# SchemaB.net
KiCad netlist of a schematic drawn in Altium Designer
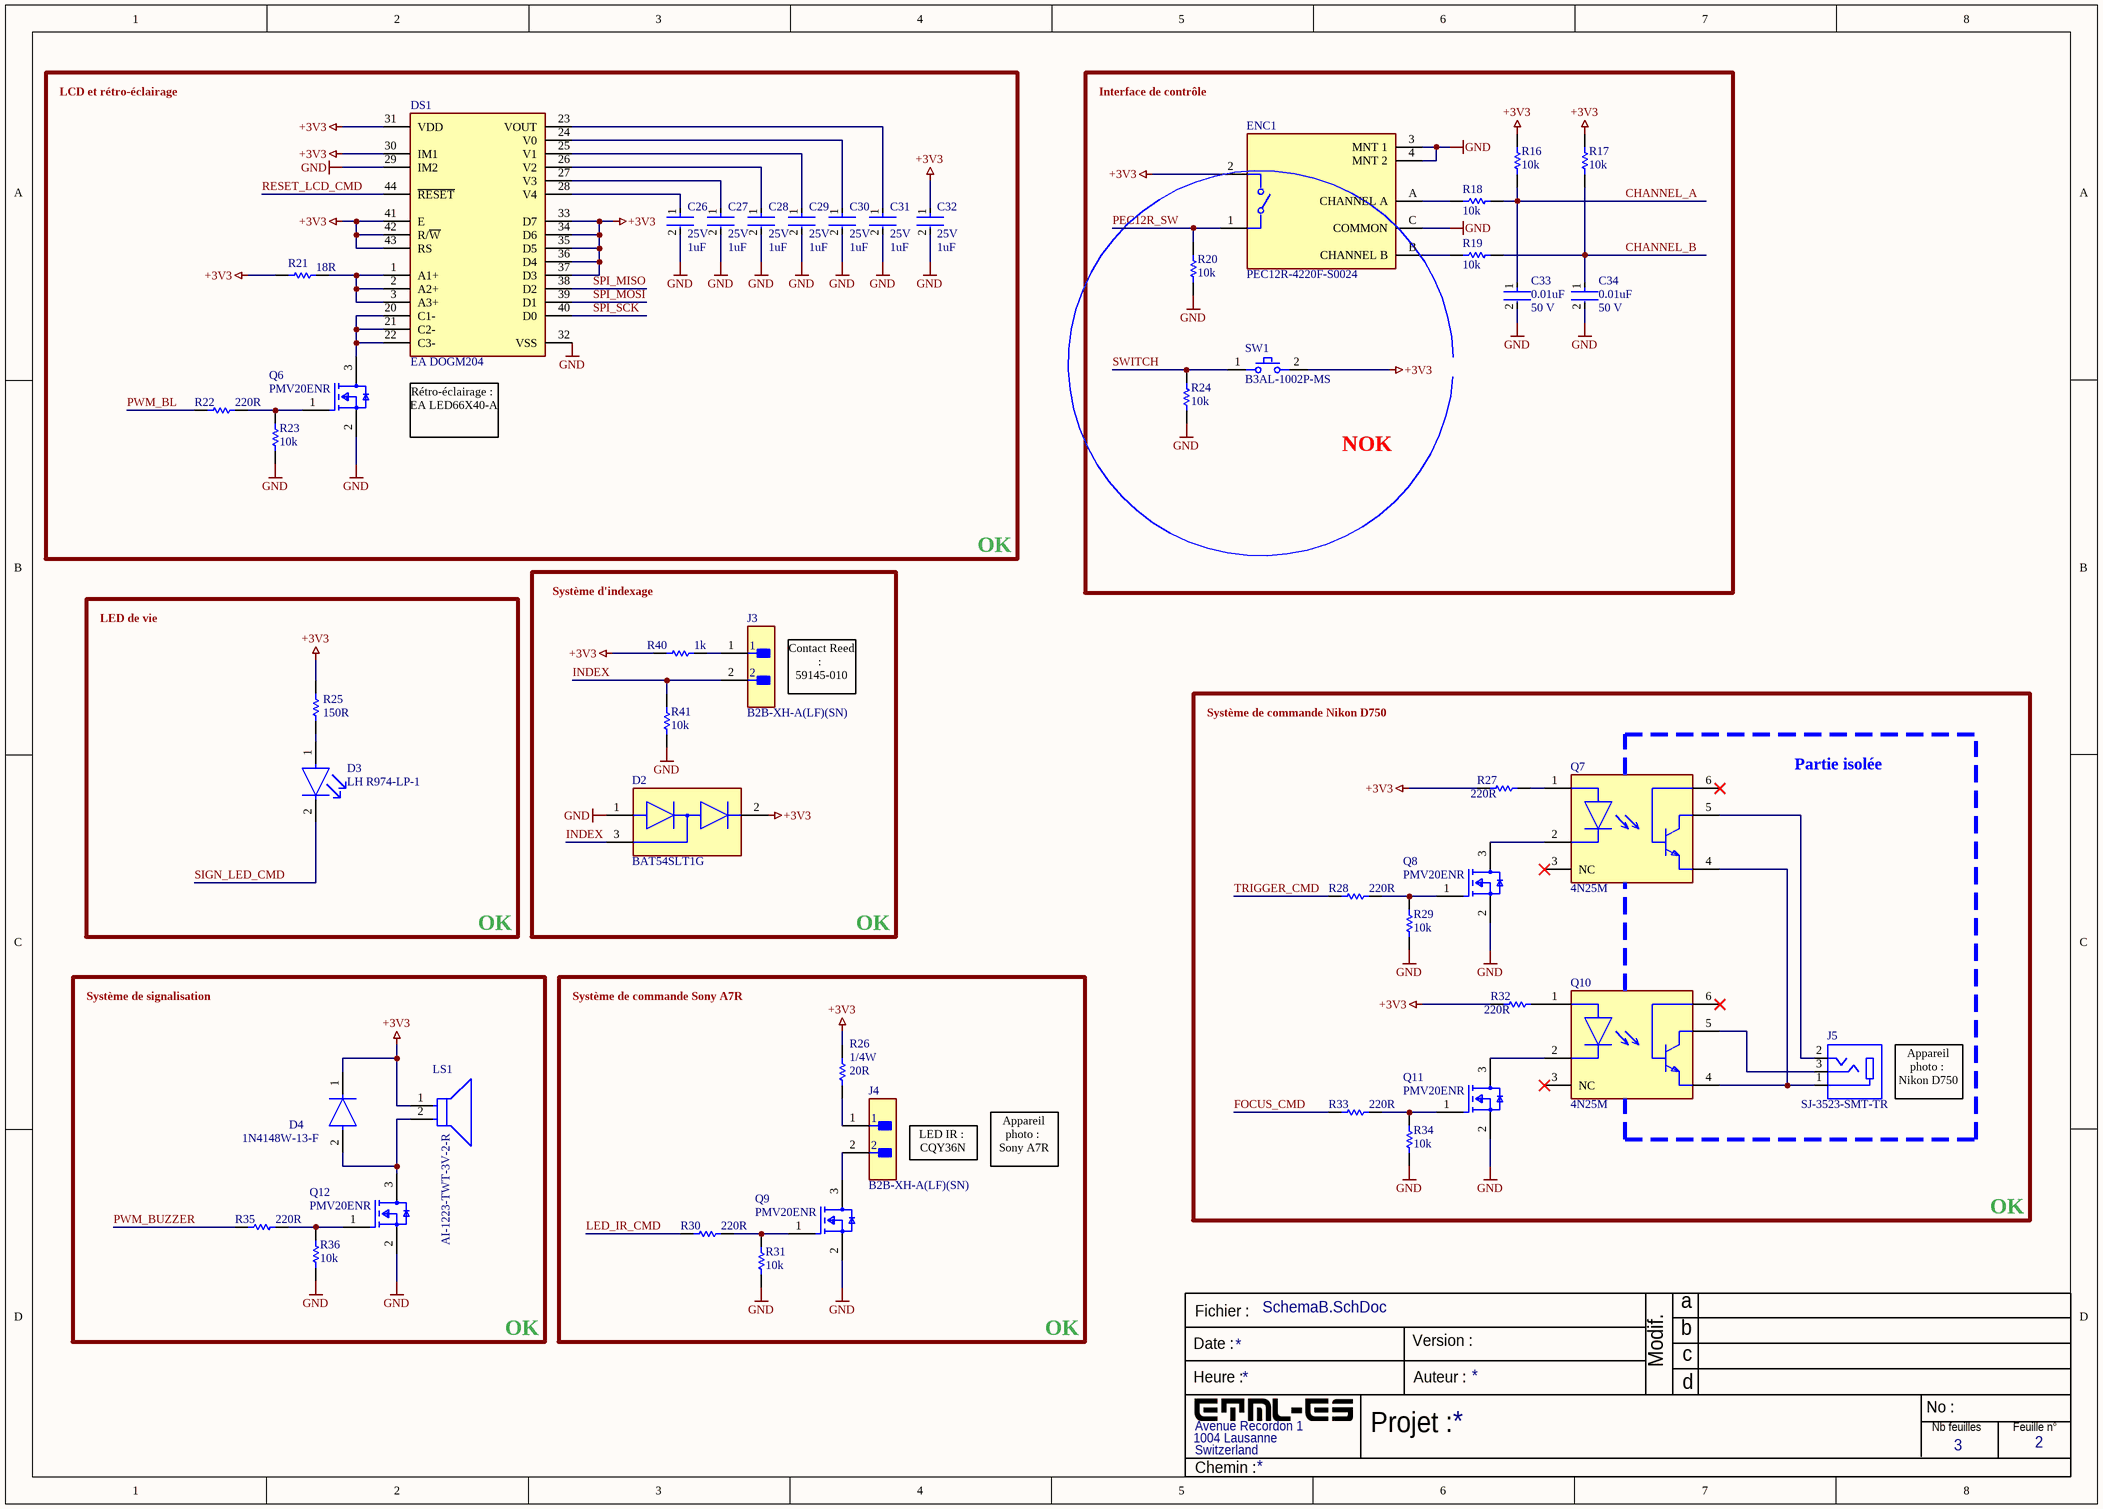
[diagram p0: SchemaB.SchDoc]

(export (version "E")
  (design (tool "Eeschema 10.0.6"))
  (components
    (comp (ref "C26")
      (value "CL21F105ZAFNNNF")
      (footprint "FP-CL21-IPC_B")
      (description "CL21 Series 0805 1uF 25V -20/+80% Tolerance Y5V Multilayer Ceramic Chip Capacitor")
      (fields
        (field (name "VOLTAGE RATING") "25V")
        (field (name "CAPACITANCE") "1uF")
        (field (name "TOLERANCE") "80%")
      )
      (libsource (lib "Altium Content Vault") (part "b4654b650e69147ec39a6b967a45e02"))
    )
    (comp (ref "C27")
      (value "CL21F105ZAFNNNF")
      (footprint "FP-CL21-IPC_B")
      (description "CL21 Series 0805 1uF 25V -20/+80% Tolerance Y5V Multilayer Ceramic Chip Capacitor")
      (fields
        (field (name "VOLTAGE RATING") "25V")
        (field (name "CAPACITANCE") "1uF")
        (field (name "TOLERANCE") "80%")
      )
      (libsource (lib "Altium Content Vault") (part "b4654b650e69147ec39a6b967a45e02"))
    )
    (comp (ref "C28")
      (value "CL21F105ZAFNNNF")
      (footprint "FP-CL21-IPC_B")
      (description "CL21 Series 0805 1uF 25V -20/+80% Tolerance Y5V Multilayer Ceramic Chip Capacitor")
      (fields
        (field (name "VOLTAGE RATING") "25V")
        (field (name "CAPACITANCE") "1uF")
        (field (name "TOLERANCE") "80%")
      )
      (libsource (lib "Altium Content Vault") (part "b4654b650e69147ec39a6b967a45e02"))
    )
    (comp (ref "C29")
      (value "CL21F105ZAFNNNF")
      (footprint "FP-CL21-IPC_B")
      (description "CL21 Series 0805 1uF 25V -20/+80% Tolerance Y5V Multilayer Ceramic Chip Capacitor")
      (fields
        (field (name "VOLTAGE RATING") "25V")
        (field (name "CAPACITANCE") "1uF")
        (field (name "TOLERANCE") "80%")
      )
      (libsource (lib "Altium Content Vault") (part "b4654b650e69147ec39a6b967a45e02"))
    )
    (comp (ref "C30")
      (value "CL21F105ZAFNNNF")
      (footprint "FP-CL21-IPC_B")
      (description "CL21 Series 0805 1uF 25V -20/+80% Tolerance Y5V Multilayer Ceramic Chip Capacitor")
      (fields
        (field (name "VOLTAGE RATING") "25V")
        (field (name "CAPACITANCE") "1uF")
        (field (name "TOLERANCE") "80%")
      )
      (libsource (lib "Altium Content Vault") (part "b4654b650e69147ec39a6b967a45e02"))
    )
    (comp (ref "C31")
      (value "CL21F105ZAFNNNF")
      (footprint "FP-CL21-IPC_B")
      (description "CL21 Series 0805 1uF 25V -20/+80% Tolerance Y5V Multilayer Ceramic Chip Capacitor")
      (fields
        (field (name "VOLTAGE RATING") "25V")
        (field (name "CAPACITANCE") "1uF")
        (field (name "TOLERANCE") "80%")
      )
      (libsource (lib "Altium Content Vault") (part "b4654b650e69147ec39a6b967a45e02"))
    )
    (comp (ref "C32")
      (value "CL21F105ZAFNNNF")
      (footprint "FP-CL21-IPC_B")
      (description "CL21 Series 0805 1uF 25V -20/+80% Tolerance Y5V Multilayer Ceramic Chip Capacitor")
      (fields
        (field (name "VOLTAGE RATING") "25V")
        (field (name "CAPACITANCE") "1uF")
        (field (name "TOLERANCE") "80%")
      )
      (libsource (lib "Altium Content Vault") (part "b4654b650e69147ec39a6b967a45e02"))
    )
    (comp (ref "C33")
      (value "0.01uF")
      (footprint "FP-C0805C-DN-MFG")
      (description "CAP CER SMD 0805 .01UF X7R 5% 50")
      (fields
        (field (name "MANUFACTURER PART NUMBER") "C0805C103J5RAC7210")
        (field (name "MANUFACTURER") "KEMET")
        (field (name "VOLTAGE RATING") "50 V")
      )
      (libsource (lib "Altium Content Vault") (part "b4654b650e69147ec39a6b967a45e02"))
    )
    (comp (ref "C34")
      (value "0.01uF")
      (footprint "FP-C0805C-DN-MFG")
      (description "CAP CER SMD 0805 .01UF X7R 5% 50")
      (fields
        (field (name "MANUFACTURER PART NUMBER") "C0805C103J5RAC7210")
        (field (name "MANUFACTURER") "KEMET")
        (field (name "VOLTAGE RATING") "50 V")
      )
      (libsource (lib "Altium Content Vault") (part "b4654b650e69147ec39a6b967a45e02"))
    )
    (comp (ref "D2")
      (value "BAT54SLT1G")
      (footprint "FP-318-08-IPC_B")
      (description "DIODE ARRAY SCHOTTKY 30V SOT23-3")
      (libsource (lib "Altium Content Vault") (part "cd4ed45a2b9de5095685adb7d6d9b5b"))
    )
    (comp (ref "D3")
      (value "LH R974-LP-1")
      (footprint "FP-LH_R974-MFG")
      (description "LED RED DIFFUSED 0805 SMD")
      (libsource (lib "Altium Content Vault") (part "ab1c01a81903e929fc6c44469aada92"))
    )
    (comp (ref "D4")
      (value "1N4148W-13-F")
      (footprint "FP-SOD123-MFG")
      (description "DIODE GEN PURP 100V 150MA SOD123")
      (fields
        (field (name "OCTOPART") "https://octopart.com/1n4148w-13-f-diodes+inc.-2359612")
        (field (name "MANUFACTURER") "Diodes Inc.")
      )
      (libsource (lib "Altium Content Vault") (part "d7152d700b627762746794eb795d46e"))
    )
    (comp (ref "DS1")
      (value "EA DOGM204")
      (footprint "EA DOGM204")
      (libsource (lib "SymbLib") (part "EA DOGM204"))
    )
    (comp (ref "ENC1")
      (value "PEC12R-4220F-S0024")
      (footprint "FP-PEC12R-4220F-S0024-MFG")
      (description "ROTARY ENCODER MECHANICAL 24PPR")
      (libsource (lib "Altium Content Vault") (part "94c173c7df275f4241826ab5d869309"))
    )
    (comp (ref "J3")
      (value "B2B-XH-A(LF)(SN)")
      (footprint "FP-B2B-XH-A_LF_SN-MFG")
      (description "CONN HEADER VERT 2POS 2.5MM")
      (libsource (lib "Altium Content Vault") (part "3bc925449376181038e59eaffc5286c"))
    )
    (comp (ref "J4")
      (value "B2B-XH-A(LF)(SN)")
      (footprint "FP-B2B-XH-A_LF_SN-MFG")
      (description "CONN HEADER VERT 2POS 2.5MM")
      (libsource (lib "Altium Content Vault") (part "3bc925449376181038e59eaffc5286c"))
    )
    (comp (ref "J5")
      (value "SJ-3523-SMT-TR")
      (footprint "CUI_SJ-3523-SMT")
      (libsource (lib "SymbLib") (part "SJ-3523-SMT"))
    )
    (comp (ref "LS1")
      (value "AI-1223-TWT-3V-2-R")
      (footprint "FP-AI-1223-TWT-3V-2-R-MFG")
      (description "BUZZER MAGNETIC 3V 12MM TH")
      (libsource (lib "Altium Content Vault") (part "1973c4b650225fd2ddacaff6b763965"))
    )
    (comp (ref "Q6")
      (value "PMV20ENR")
      (footprint "FP-SOT23-MFG")
      (description "MOSFET N-CH 30V SOT23")
      (libsource (lib "Altium Content Vault") (part "0a9ea7c96deaaede766a5b531c28de0"))
    )
    (comp (ref "Q7")
      (value "4N25M")
      (footprint "FP-646BX-MFG")
      (description "4N25M Optocoupler DC-IN 1-CH Transistor With Base DC-OUT 6-Pin PDIP Tube - Bulk")
      (libsource (lib "Altium Content Vault") (part "60cd882971725889b330b3d3aa4682b"))
    )
    (comp (ref "Q8")
      (value "PMV20ENR")
      (footprint "FP-SOT23-MFG")
      (description "MOSFET N-CH 30V SOT23")
      (libsource (lib "Altium Content Vault") (part "0a9ea7c96deaaede766a5b531c28de0"))
    )
    (comp (ref "Q9")
      (value "PMV20ENR")
      (footprint "FP-SOT23-MFG")
      (description "MOSFET N-CH 30V SOT23")
      (libsource (lib "Altium Content Vault") (part "0a9ea7c96deaaede766a5b531c28de0"))
    )
    (comp (ref "Q10")
      (value "4N25M")
      (footprint "FP-646BX-MFG")
      (description "4N25M Optocoupler DC-IN 1-CH Transistor With Base DC-OUT 6-Pin PDIP Tube - Bulk")
      (libsource (lib "Altium Content Vault") (part "60cd882971725889b330b3d3aa4682b"))
    )
    (comp (ref "Q11")
      (value "PMV20ENR")
      (footprint "FP-SOT23-MFG")
      (description "MOSFET N-CH 30V SOT23")
      (libsource (lib "Altium Content Vault") (part "0a9ea7c96deaaede766a5b531c28de0"))
    )
    (comp (ref "Q12")
      (value "PMV20ENR")
      (footprint "FP-SOT23-MFG")
      (description "MOSFET N-CH 30V SOT23")
      (libsource (lib "Altium Content Vault") (part "0a9ea7c96deaaede766a5b531c28de0"))
    )
    (comp (ref "R16")
      (value "RC0805JR-0710KL")
      (footprint "RESC2013X60X35ML10T20")
      (description "Chip Resistor, 10 KOhm, +/- 5%, 0.125 W, -55 to 155 degC, 0805 (2012 Metric), RoHS, Tape and Reel")
      (fields (field (name "MANUFACTURER") "Yageo") (field (name "RESISTANCE") "10k"))
      (libsource (lib "Altium Content Vault") (part "RES-2"))
    )
    (comp (ref "R17")
      (value "RC0805JR-0710KL")
      (footprint "RESC2013X60X35ML10T20")
      (description "Chip Resistor, 10 KOhm, +/- 5%, 0.125 W, -55 to 155 degC, 0805 (2012 Metric), RoHS, Tape and Reel")
      (fields (field (name "MANUFACTURER") "Yageo") (field (name "RESISTANCE") "10k"))
      (libsource (lib "Altium Content Vault") (part "RES-2"))
    )
    (comp (ref "R18")
      (value "RC0805JR-0710KL")
      (footprint "RESC2013X60X35ML10T20")
      (description "Chip Resistor, 10 KOhm, +/- 5%, 0.125 W, -55 to 155 degC, 0805 (2012 Metric), RoHS, Tape and Reel")
      (fields (field (name "MANUFACTURER") "Yageo") (field (name "RESISTANCE") "10k"))
      (libsource (lib "Altium Content Vault") (part "RES-2"))
    )
    (comp (ref "R19")
      (value "RC0805JR-0710KL")
      (footprint "RESC2013X60X35ML10T20")
      (description "Chip Resistor, 10 KOhm, +/- 5%, 0.125 W, -55 to 155 degC, 0805 (2012 Metric), RoHS, Tape and Reel")
      (fields (field (name "MANUFACTURER") "Yageo") (field (name "RESISTANCE") "10k"))
      (libsource (lib "Altium Content Vault") (part "RES-2"))
    )
    (comp (ref "R20")
      (value "RC0805JR-0710KL")
      (footprint "RESC2013X60X35ML10T20")
      (description "Chip Resistor, 10 KOhm, +/- 5%, 0.125 W, -55 to 155 degC, 0805 (2012 Metric), RoHS, Tape and Reel")
      (fields (field (name "MANUFACTURER") "Yageo") (field (name "RESISTANCE") "10k"))
      (libsource (lib "Altium Content Vault") (part "RES-2"))
    )
    (comp (ref "R21")
      (value "18R")
      (footprint "RESC2013X70X40ML20T20")
      (fields (field (name "MANUFACTURER") "Panasonic") (field (name "PART NUMBER") "ERJ6ENF18R0V"))
      (libsource (lib "Altium Content Vault") (part "RES"))
    )
    (comp (ref "R22")
      (value "220R")
      (footprint "RESC2013X70X40NL20T20")
      (fields (field (name "PART NUMBER") "ERJ6ENF2200V") (field (name "MANUFACTURER") "Panasonic"))
      (libsource (lib "Altium Content Vault") (part "RES"))
    )
    (comp (ref "R23")
      (value "RC0805JR-0710KL")
      (footprint "RESC2013X60X35ML10T20")
      (description "Chip Resistor, 10 KOhm, +/- 5%, 0.125 W, -55 to 155 degC, 0805 (2012 Metric), RoHS, Tape and Reel")
      (fields (field (name "MANUFACTURER") "Yageo") (field (name "RESISTANCE") "10k"))
      (libsource (lib "Altium Content Vault") (part "RES-2"))
    )
    (comp (ref "R24")
      (value "RC0805JR-0710KL")
      (footprint "RESC2013X60X35ML10T20")
      (description "Chip Resistor, 10 KOhm, +/- 5%, 0.125 W, -55 to 155 degC, 0805 (2012 Metric), RoHS, Tape and Reel")
      (fields (field (name "MANUFACTURER") "Yageo") (field (name "RESISTANCE") "10k"))
      (libsource (lib "Altium Content Vault") (part "RES-2"))
    )
    (comp (ref "R25")
      (value "150R")
      (footprint "RESC2013X60X35ML10T20")
      (fields (field (name "MANUFACTURER") "Yageo") (field (name "PART NUMBER") "RC0805JR-0775RL"))
      (libsource (lib "Altium Content Vault") (part "RES"))
    )
    (comp (ref "R26")
      (value "20R")
      (footprint "RESC2013X60X30ML20T20")
      (fields
        (field (name "PART NUMBER") "RK73B2ATTD200J")
        (field (name "MANUFACTURER") "KOA Speer")
        (field (name "PUISSANCE") "1/4W")
      )
      (libsource (lib "Altium Content Vault") (part "RES"))
    )
    (comp (ref "R27")
      (value "220R")
      (footprint "RESC2013X50X30NL20T20")
      (fields (field (name "PART NUMBER") "CRCW0805210RFKEA") (field (name "MANUFACTURER") "Vishay Dale"))
      (libsource (lib "Altium Content Vault") (part "RES"))
    )
    (comp (ref "R28")
      (value "220R")
      (footprint "RESC2013X70X40NL20T20")
      (fields (field (name "PART NUMBER") "ERJ6ENF2200V") (field (name "MANUFACTURER") "Panasonic"))
      (libsource (lib "Altium Content Vault") (part "RES"))
    )
    (comp (ref "R29")
      (value "RC0805JR-0710KL")
      (footprint "RESC2013X60X35ML10T20")
      (description "Chip Resistor, 10 KOhm, +/- 5%, 0.125 W, -55 to 155 degC, 0805 (2012 Metric), RoHS, Tape and Reel")
      (fields (field (name "MANUFACTURER") "Yageo") (field (name "RESISTANCE") "10k"))
      (libsource (lib "Altium Content Vault") (part "RES-2"))
    )
    (comp (ref "R30")
      (value "220R")
      (footprint "RESC2013X70X40NL20T20")
      (fields (field (name "PART NUMBER") "ERJ6ENF2200V") (field (name "MANUFACTURER") "Panasonic"))
      (libsource (lib "Altium Content Vault") (part "RES"))
    )
    (comp (ref "R31")
      (value "RC0805JR-0710KL")
      (footprint "RESC2013X60X35ML10T20")
      (description "Chip Resistor, 10 KOhm, +/- 5%, 0.125 W, -55 to 155 degC, 0805 (2012 Metric), RoHS, Tape and Reel")
      (fields (field (name "MANUFACTURER") "Yageo") (field (name "RESISTANCE") "10k"))
      (libsource (lib "Altium Content Vault") (part "RES-2"))
    )
    (comp (ref "R32")
      (value "220R")
      (footprint "RESC2013X50X30NL20T20")
      (fields (field (name "PART NUMBER") "CRCW0805210RFKEA") (field (name "MANUFACTURER") "Vishay Dale"))
      (libsource (lib "Altium Content Vault") (part "RES"))
    )
    (comp (ref "R33")
      (value "220R")
      (footprint "RESC2013X70X40NL20T20")
      (fields (field (name "PART NUMBER") "ERJ6ENF2200V") (field (name "MANUFACTURER") "Panasonic"))
      (libsource (lib "Altium Content Vault") (part "RES"))
    )
    (comp (ref "R34")
      (value "RC0805JR-0710KL")
      (footprint "RESC2013X60X35ML10T20")
      (description "Chip Resistor, 10 KOhm, +/- 5%, 0.125 W, -55 to 155 degC, 0805 (2012 Metric), RoHS, Tape and Reel")
      (fields (field (name "MANUFACTURER") "Yageo") (field (name "RESISTANCE") "10k"))
      (libsource (lib "Altium Content Vault") (part "RES-2"))
    )
    (comp (ref "R35")
      (value "220R")
      (footprint "RESC2013X70X40NL20T20")
      (fields (field (name "PART NUMBER") "ERJ6ENF2200V") (field (name "MANUFACTURER") "Panasonic"))
      (libsource (lib "Altium Content Vault") (part "RES"))
    )
    (comp (ref "R36")
      (value "RC0805JR-0710KL")
      (footprint "RESC2013X60X35ML10T20")
      (description "Chip Resistor, 10 KOhm, +/- 5%, 0.125 W, -55 to 155 degC, 0805 (2012 Metric), RoHS, Tape and Reel")
      (fields (field (name "MANUFACTURER") "Yageo") (field (name "RESISTANCE") "10k"))
      (libsource (lib "Altium Content Vault") (part "RES-2"))
    )
    (comp (ref "R40")
      (value "RC0805FR-071KL")
      (footprint "RESC2013X60X35ML10T20")
      (description "Chip Resistor, 1 KOhm, +/- 1%, 125 mW, -55 to 155 degC, 0805 (2012 Metric), RoHS, Tape and Reel")
      (fields
        (field (name "RESISTANCE") "1k")
        (field (name "TOLERANCE") "1%")
        (field (name "MANUFACTURER") "Yageo")
      )
      (libsource (lib "Altium Content Vault") (part "RES-2"))
    )
    (comp (ref "R41")
      (value "RC0805JR-0710KL")
      (footprint "RESC2013X60X35ML10T20")
      (description "Chip Resistor, 10 KOhm, +/- 5%, 0.125 W, -55 to 155 degC, 0805 (2012 Metric), RoHS, Tape and Reel")
      (fields (field (name "MANUFACTURER") "Yageo") (field (name "RESISTANCE") "10k"))
      (libsource (lib "Altium Content Vault") (part "RES-2"))
    )
    (comp (ref "SW1")
      (value "B3AL-1002P-MS")
      (footprint "FP-B3AL-1002P-MS-MFG")
      (description "SWITCH TACTILE SPST-NO 0.05A 16V")
      (libsource (lib "Altium Content Vault") (part "69e8347f6a24c021ef43a914a4df441"))
    )
  )
  (nets
    (net (code "1") (name "+3V3") (class "Default")
      (node (ref "C32") (pin "1") (pinfunction "1_1") (pintype "passive"))
      (node (ref "D2") (pin "2") (pinfunction "C_2") (pintype "passive"))
      (node (ref "D4") (pin "1") (pinfunction "C_1") (pintype "passive"))
      (node (ref "DS1") (pin "30") (pinfunction "IM1_30") (pintype "passive"))
      (node (ref "DS1") (pin "31") (pinfunction "VDD_31") (pintype "passive"))
      (node (ref "DS1") (pin "33") (pinfunction "D7_33") (pintype "passive"))
      (node (ref "DS1") (pin "34") (pinfunction "D6_34") (pintype "passive"))
      (node (ref "DS1") (pin "35") (pinfunction "D5_35") (pintype "passive"))
      (node (ref "DS1") (pin "36") (pinfunction "D4_36") (pintype "passive"))
      (node (ref "DS1") (pin "37") (pinfunction "D3_37") (pintype "passive"))
      (node (ref "DS1") (pin "41") (pinfunction "E_41") (pintype "passive"))
      (node (ref "DS1") (pin "42") (pinfunction "R/~{W}_42") (pintype "passive"))
      (node (ref "DS1") (pin "43") (pinfunction "RS_43") (pintype "passive"))
      (node (ref "ENC1") (pin "2") (pinfunction "2_2") (pintype "passive"))
      (node (ref "LS1") (pin "1") (pinfunction "C_1") (pintype "passive"))
      (node (ref "R16") (pin "1") (pinfunction "1_1") (pintype "passive"))
      (node (ref "R17") (pin "1") (pinfunction "1_1") (pintype "passive"))
      (node (ref "R21") (pin "1") (pinfunction "1_1") (pintype "passive"))
      (node (ref "R25") (pin "2") (pinfunction "2_2") (pintype "passive"))
      (node (ref "R26") (pin "2") (pinfunction "2_2") (pintype "passive"))
      (node (ref "R27") (pin "1") (pinfunction "1_1") (pintype "passive"))
      (node (ref "R32") (pin "1") (pinfunction "1_1") (pintype "passive"))
      (node (ref "R40") (pin "1") (pinfunction "1_1") (pintype "passive"))
      (node (ref "SW1") (pin "2") (pinfunction "2_2") (pintype "passive"))
    )
    (net (code "2") (name "/CHANNEL_A") (class "Default")
      (node (ref "C33") (pin "1") (pinfunction "1_1") (pintype "passive"))
      (node (ref "R16") (pin "2") (pinfunction "2_2") (pintype "passive"))
      (node (ref "R18") (pin "1") (pinfunction "1_1") (pintype "passive"))
    )
    (net (code "3") (name "/CHANNEL_B") (class "Default")
      (node (ref "C34") (pin "1") (pinfunction "1_1") (pintype "passive"))
      (node (ref "R17") (pin "2") (pinfunction "2_2") (pintype "passive"))
      (node (ref "R19") (pin "1") (pinfunction "1_1") (pintype "passive"))
    )
    (net (code "4") (name "/FOCUS_CMD") (class "Default")
      (node (ref "R33") (pin "1") (pinfunction "1_1") (pintype "passive"))
    )
    (net (code "5") (name "/INDEX") (class "Default")
      (node (ref "D2") (pin "3") (pinfunction "CATHODE/ANODE_3") (pintype "passive"))
      (node (ref "J3") (pin "2") (pinfunction "2_2") (pintype "passive"))
      (node (ref "R41") (pin "1") (pinfunction "1_1") (pintype "passive"))
    )
    (net (code "6") (name "/LED_IR_CMD") (class "Default")
      (node (ref "R30") (pin "1") (pinfunction "1_1") (pintype "passive"))
    )
    (net (code "7") (name "/PEC12R_SW") (class "Default")
      (node (ref "ENC1") (pin "1") (pinfunction "1_1") (pintype "passive"))
      (node (ref "R20") (pin "1") (pinfunction "1_1") (pintype "passive"))
    )
    (net (code "8") (name "/PWM_BL") (class "Default")
      (node (ref "R22") (pin "1") (pinfunction "1_1") (pintype "passive"))
    )
    (net (code "9") (name "/PWM_BUZZER") (class "Default")
      (node (ref "R35") (pin "1") (pinfunction "1_1") (pintype "passive"))
    )
    (net (code "10") (name "/RESET_LCD_CMD") (class "Default")
      (node (ref "DS1") (pin "44") (pinfunction "~{RESET}_44") (pintype "passive"))
    )
    (net (code "11") (name "/SIGN_LED_CMD") (class "Default")
      (node (ref "D3") (pin "2") (pinfunction "C_2") (pintype "passive"))
    )
    (net (code "12") (name "/SPI_MISO") (class "Default")
      (node (ref "DS1") (pin "38") (pinfunction "D2_38") (pintype "passive"))
    )
    (net (code "13") (name "/SPI_MOSI") (class "Default")
      (node (ref "DS1") (pin "39") (pinfunction "D1_39") (pintype "passive"))
    )
    (net (code "14") (name "/SPI_SCK") (class "Default")
      (node (ref "DS1") (pin "40") (pinfunction "D0_40") (pintype "passive"))
    )
    (net (code "15") (name "/SWITCH") (class "Default")
      (node (ref "R24") (pin "1") (pinfunction "1_1") (pintype "passive"))
      (node (ref "SW1") (pin "1") (pinfunction "1_1") (pintype "passive"))
    )
    (net (code "16") (name "/TRIGGER_CMD") (class "Default")
      (node (ref "R28") (pin "1") (pinfunction "1_1") (pintype "passive"))
    )
    (net (code "17") (name "GND") (class "Default")
      (node (ref "C26") (pin "2") (pinfunction "2_2") (pintype "passive"))
      (node (ref "C27") (pin "2") (pinfunction "2_2") (pintype "passive"))
      (node (ref "C28") (pin "2") (pinfunction "2_2") (pintype "passive"))
      (node (ref "C29") (pin "2") (pinfunction "2_2") (pintype "passive"))
      (node (ref "C30") (pin "2") (pinfunction "2_2") (pintype "passive"))
      (node (ref "C31") (pin "2") (pinfunction "2_2") (pintype "passive"))
      (node (ref "C32") (pin "2") (pinfunction "2_2") (pintype "passive"))
      (node (ref "C33") (pin "2") (pinfunction "2_2") (pintype "passive"))
      (node (ref "C34") (pin "2") (pinfunction "2_2") (pintype "passive"))
      (node (ref "D2") (pin "1") (pinfunction "A_1") (pintype "passive"))
      (node (ref "DS1") (pin "29") (pinfunction "IM2_29") (pintype "passive"))
      (node (ref "DS1") (pin "32") (pinfunction "VSS_32") (pintype "passive"))
      (node (ref "ENC1") (pin "3") (pinfunction "MNT_1_3") (pintype "passive"))
      (node (ref "ENC1") (pin "4") (pinfunction "MNT_2_4") (pintype "passive"))
      (node (ref "ENC1") (pin "C") (pinfunction "COMMON_C") (pintype "passive"))
      (node (ref "Q11") (pin "2") (pinfunction "S_2") (pintype "passive"))
      (node (ref "Q12") (pin "2") (pinfunction "S_2") (pintype "passive"))
      (node (ref "Q6") (pin "2") (pinfunction "S_2") (pintype "passive"))
      (node (ref "Q8") (pin "2") (pinfunction "S_2") (pintype "passive"))
      (node (ref "Q9") (pin "2") (pinfunction "S_2") (pintype "passive"))
      (node (ref "R20") (pin "2") (pinfunction "2_2") (pintype "passive"))
      (node (ref "R23") (pin "1") (pinfunction "1_1") (pintype "passive"))
      (node (ref "R24") (pin "2") (pinfunction "2_2") (pintype "passive"))
      (node (ref "R29") (pin "1") (pinfunction "1_1") (pintype "passive"))
      (node (ref "R31") (pin "1") (pinfunction "1_1") (pintype "passive"))
      (node (ref "R34") (pin "1") (pinfunction "1_1") (pintype "passive"))
      (node (ref "R36") (pin "1") (pinfunction "1_1") (pintype "passive"))
      (node (ref "R41") (pin "2") (pinfunction "2_2") (pintype "passive"))
    )
    (net (code "18") (name "Net-(D3-A)") (class "Default")
      (node (ref "D3") (pin "1") (pinfunction "A_1") (pintype "passive"))
      (node (ref "R25") (pin "1") (pinfunction "1_1") (pintype "passive"))
    )
    (net (code "19") (name "Net-(D4-A)") (class "Default")
      (node (ref "D4") (pin "2") (pinfunction "A_2") (pintype "passive"))
      (node (ref "LS1") (pin "2") (pinfunction "A_2") (pintype "passive"))
      (node (ref "Q12") (pin "3") (pinfunction "D_3") (pintype "passive"))
    )
    (net (code "20") (name "Net-(DS1-A1+)") (class "Default")
      (node (ref "DS1") (pin "1") (pinfunction "A1+_1") (pintype "passive"))
      (node (ref "DS1") (pin "2") (pinfunction "A2+_2") (pintype "passive"))
      (node (ref "DS1") (pin "3") (pinfunction "A3+_3") (pintype "passive"))
      (node (ref "R21") (pin "2") (pinfunction "2_2") (pintype "passive"))
    )
    (net (code "21") (name "Net-(DS1-C1-)") (class "Default")
      (node (ref "DS1") (pin "20") (pinfunction "C1-_20") (pintype "passive"))
      (node (ref "DS1") (pin "21") (pinfunction "C2-_21") (pintype "passive"))
      (node (ref "DS1") (pin "22") (pinfunction "C3-_22") (pintype "passive"))
      (node (ref "Q6") (pin "3") (pinfunction "D_3") (pintype "passive"))
    )
    (net (code "22") (name "Net-(DS1-V0)") (class "Default")
      (node (ref "C30") (pin "1") (pinfunction "1_1") (pintype "passive"))
      (node (ref "DS1") (pin "24") (pinfunction "V0_24") (pintype "passive"))
    )
    (net (code "23") (name "Net-(DS1-V1)") (class "Default")
      (node (ref "C29") (pin "1") (pinfunction "1_1") (pintype "passive"))
      (node (ref "DS1") (pin "25") (pinfunction "V1_25") (pintype "passive"))
    )
    (net (code "24") (name "Net-(DS1-V2)") (class "Default")
      (node (ref "C28") (pin "1") (pinfunction "1_1") (pintype "passive"))
      (node (ref "DS1") (pin "26") (pinfunction "V2_26") (pintype "passive"))
    )
    (net (code "25") (name "Net-(DS1-V3)") (class "Default")
      (node (ref "C27") (pin "1") (pinfunction "1_1") (pintype "passive"))
      (node (ref "DS1") (pin "27") (pinfunction "V3_27") (pintype "passive"))
    )
    (net (code "26") (name "Net-(DS1-V4)") (class "Default")
      (node (ref "C26") (pin "1") (pinfunction "1_1") (pintype "passive"))
      (node (ref "DS1") (pin "28") (pinfunction "V4_28") (pintype "passive"))
    )
    (net (code "27") (name "Net-(DS1-VOUT)") (class "Default")
      (node (ref "C31") (pin "1") (pinfunction "1_1") (pintype "passive"))
      (node (ref "DS1") (pin "23") (pinfunction "VOUT_23") (pintype "passive"))
    )
    (net (code "28") (name "Net-(ENC1-CHANNEL_A)") (class "Default")
      (node (ref "ENC1") (pin "A") (pinfunction "CHANNEL_A_A") (pintype "passive"))
      (node (ref "R18") (pin "2") (pinfunction "2_2") (pintype "passive"))
    )
    (net (code "29") (name "Net-(ENC1-CHANNEL_B)") (class "Default")
      (node (ref "ENC1") (pin "B") (pinfunction "CHANNEL_B_B") (pintype "passive"))
      (node (ref "R19") (pin "2") (pinfunction "2_2") (pintype "passive"))
    )
    (net (code "30") (name "Net-(J3-Pad1)") (class "Default")
      (node (ref "J3") (pin "1") (pinfunction "1_1") (pintype "passive"))
      (node (ref "R40") (pin "2") (pinfunction "2_2") (pintype "passive"))
    )
    (net (code "31") (name "Net-(J4-Pad1)") (class "Default")
      (node (ref "J4") (pin "1") (pinfunction "1_1") (pintype "passive"))
      (node (ref "R26") (pin "1") (pinfunction "1_1") (pintype "passive"))
    )
    (net (code "32") (name "Net-(J5-Pad2)") (class "Default")
      (node (ref "J5") (pin "2") (pinfunction "2_2") (pintype "passive"))
      (node (ref "Q7") (pin "5") (pinfunction "C_5") (pintype "passive"))
    )
    (net (code "33") (name "Net-(J5-Pad3)") (class "Default")
      (node (ref "J5") (pin "3") (pinfunction "3_3") (pintype "passive"))
      (node (ref "Q10") (pin "5") (pinfunction "C_5") (pintype "passive"))
    )
    (net (code "34") (name "Net-(Q6-G)") (class "Default")
      (node (ref "Q6") (pin "1") (pinfunction "G_1") (pintype "passive"))
      (node (ref "R22") (pin "2") (pinfunction "2_2") (pintype "passive"))
      (node (ref "R23") (pin "2") (pinfunction "2_2") (pintype "passive"))
    )
    (net (code "35") (name "Net-(Q7-A)") (class "Default")
      (node (ref "Q7") (pin "1") (pinfunction "A_1") (pintype "passive"))
      (node (ref "R27") (pin "2") (pinfunction "2_2") (pintype "passive"))
    )
    (net (code "36") (name "Net-(Q8-D)") (class "Default")
      (node (ref "Q7") (pin "2") (pinfunction "C_2") (pintype "passive"))
      (node (ref "Q8") (pin "3") (pinfunction "D_3") (pintype "passive"))
    )
    (net (code "37") (name "Net-(Q8-G)") (class "Default")
      (node (ref "Q8") (pin "1") (pinfunction "G_1") (pintype "passive"))
      (node (ref "R28") (pin "2") (pinfunction "2_2") (pintype "passive"))
      (node (ref "R29") (pin "2") (pinfunction "2_2") (pintype "passive"))
    )
    (net (code "38") (name "Net-(Q9-D)") (class "Default")
      (node (ref "J4") (pin "2") (pinfunction "2_2") (pintype "passive"))
      (node (ref "Q9") (pin "3") (pinfunction "D_3") (pintype "passive"))
    )
    (net (code "39") (name "Net-(Q9-G)") (class "Default")
      (node (ref "Q9") (pin "1") (pinfunction "G_1") (pintype "passive"))
      (node (ref "R30") (pin "2") (pinfunction "2_2") (pintype "passive"))
      (node (ref "R31") (pin "2") (pinfunction "2_2") (pintype "passive"))
    )
    (net (code "40") (name "Net-(Q10-A)") (class "Default")
      (node (ref "Q10") (pin "1") (pinfunction "A_1") (pintype "passive"))
      (node (ref "R32") (pin "2") (pinfunction "2_2") (pintype "passive"))
    )
    (net (code "41") (name "Net-(Q10-E)") (class "Default")
      (node (ref "J5") (pin "1") (pinfunction "1_1") (pintype "passive"))
      (node (ref "Q10") (pin "4") (pinfunction "E_4") (pintype "passive"))
      (node (ref "Q7") (pin "4") (pinfunction "E_4") (pintype "passive"))
    )
    (net (code "42") (name "Net-(Q11-D)") (class "Default")
      (node (ref "Q10") (pin "2") (pinfunction "C_2") (pintype "passive"))
      (node (ref "Q11") (pin "3") (pinfunction "D_3") (pintype "passive"))
    )
    (net (code "43") (name "Net-(Q11-G)") (class "Default")
      (node (ref "Q11") (pin "1") (pinfunction "G_1") (pintype "passive"))
      (node (ref "R33") (pin "2") (pinfunction "2_2") (pintype "passive"))
      (node (ref "R34") (pin "2") (pinfunction "2_2") (pintype "passive"))
    )
    (net (code "44") (name "Net-(Q12-G)") (class "Default")
      (node (ref "Q12") (pin "1") (pinfunction "G_1") (pintype "passive"))
      (node (ref "R35") (pin "2") (pinfunction "2_2") (pintype "passive"))
      (node (ref "R36") (pin "2") (pinfunction "2_2") (pintype "passive"))
    )
    (net (code "45") (name "unconnected-(Q7-B-Pad6)") (class "Default")
      (node (ref "Q7") (pin "6") (pinfunction "B_6") (pintype "passive+no_connect"))
    )
    (net (code "46") (name "unconnected-(Q7-NC-Pad3)") (class "Default")
      (node (ref "Q7") (pin "3") (pinfunction "NC_3") (pintype "passive+no_connect"))
    )
    (net (code "47") (name "unconnected-(Q10-B-Pad6)") (class "Default")
      (node (ref "Q10") (pin "6") (pinfunction "B_6") (pintype "passive+no_connect"))
    )
    (net (code "48") (name "unconnected-(Q10-NC-Pad3)") (class "Default")
      (node (ref "Q10") (pin "3") (pinfunction "NC_3") (pintype "passive+no_connect"))
    )
  )
)
